# CATS-GS-MCU.net
KiCad netlist of a schematic drawn in Altium Designer
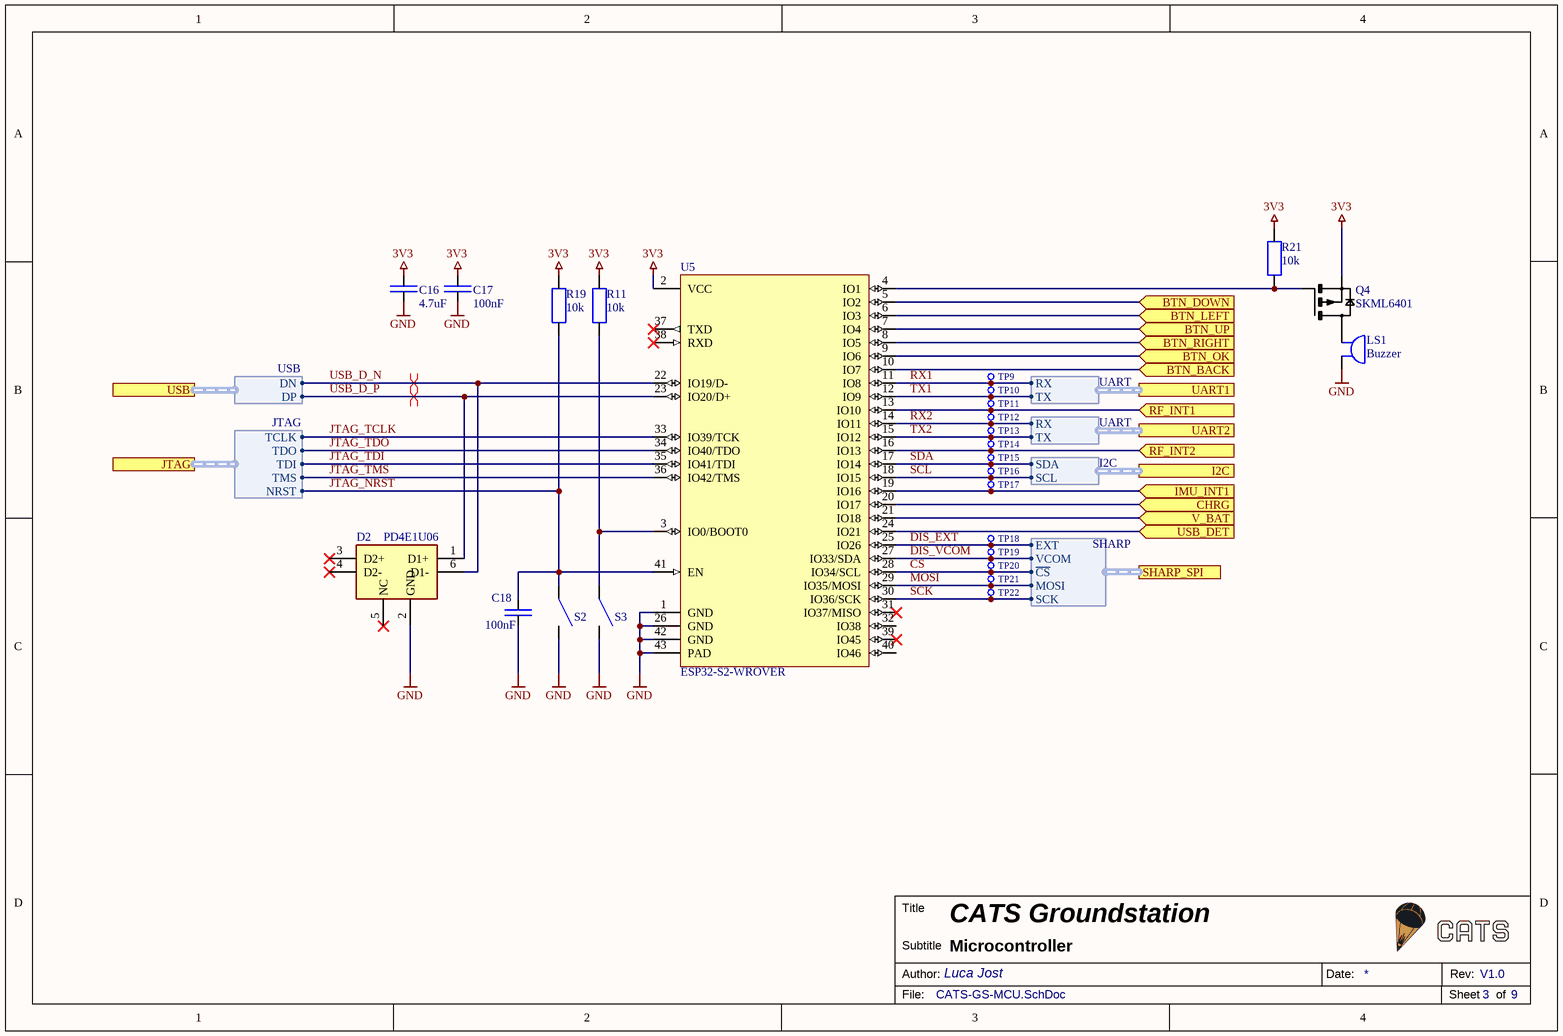
[diagram p0: CATS-GS-MCU.SchDoc]

(export (version "E")
  (design (tool "Eeschema 10.0.6"))
  (components
    (comp (ref "C16")
      (value "4.7uF")
      (footprint "SMD Keramikkondensator 0402")
      (description "SMD Ceramic Capacitor E6")
      (libsource (lib "CATS-EUROC") (part "E6 - 4.7uF"))
    )
    (comp (ref "C17")
      (value "100nF")
      (footprint "SMD Keramikkondensator 0402")
      (description "SMD Ceramic Capacitor E6")
      (libsource (lib "CATS-EUROC") (part "E6 - 100nF"))
    )
    (comp (ref "C18")
      (value "100nF")
      (footprint "SMD Keramikkondensator 0402")
      (description "SMD Ceramic Capacitor E6")
      (libsource (lib "CATS-EUROC") (part "E6 - 100nF"))
    )
    (comp (ref "D2")
      (value "PD4E1U06")
      (footprint "SMD IC SOT-363 (SC-70-6)")
      (description "Unidirectional 3A (8/20us) 15V (Typ) 6.5V 5.5V (Max) SOT-363 ESD Protection Devices ROHS")
      (libsource (lib "Fleet-Monitor") (part "PD4E1U06DCKR"))
    )
    (comp (ref "LS1")
      (value "Buzzer")
      (footprint "SMD BUZZER CMT-8504")
      (description "Buzzers Indicator, Internally Driven Piezo 12V 10mA 3kHz 100dB @ 12V, 10cm Through Hole PC Pins")
      (libsource (lib "Other") (part "Buzzer"))
    )
    (comp (ref "Q4")
      (value "SKML6401")
      (footprint "SMD MOSFET SOT-23")
      (description "P Channel MOSFET, 16V 3A, SOT-23")
      (libsource (lib "Electronic Switches") (part "SKML6401"))
    )
    (comp (ref "R11")
      (value "10k")
      (footprint "SMD Widerstand 0402")
      (description "SMD Chip Resistor E24")
      (libsource (lib "Resistors-E24") (part "E24 - 10k"))
    )
    (comp (ref "R19")
      (value "10k")
      (footprint "SMD Widerstand 0402")
      (description "SMD Chip Resistor E24")
      (libsource (lib "Resistors-E24") (part "E24 - 10k"))
    )
    (comp (ref "R21")
      (value "10k")
      (footprint "SMD Widerstand 0402")
      (description "SMD Chip Resistor E24")
      (libsource (lib "Resistors-E24") (part "E24 - 10k"))
    )
    (comp (ref "S2")
      (value "SMD-Button")
      (footprint "SMD Button 2.5x3x1.2")
      (description "Button SPST")
      (libsource (lib "CATS-EUROC") (part "Button 3mmx2.5mm"))
    )
    (comp (ref "S3")
      (value "SMD-Button")
      (footprint "SMD Button 2.5x3x1.2")
      (description "Button SPST")
      (libsource (lib "CATS-EUROC") (part "Button 3mmx2.5mm"))
    )
    (comp (ref "TP9")
      (value "X-TP")
      (footprint "SMD Testpoint 1mm")
      (description "Testpunkt")
      (libsource (lib "VLD-Monitor_V1.0") (part "X-TP"))
    )
    (comp (ref "TP10")
      (value "X-TP")
      (footprint "SMD Testpoint 1mm")
      (description "Testpunkt")
      (libsource (lib "VLD-Monitor_V1.0") (part "X-TP"))
    )
    (comp (ref "TP11")
      (value "X-TP")
      (footprint "SMD Testpoint 1mm")
      (description "Testpunkt")
      (libsource (lib "VLD-Monitor_V1.0") (part "X-TP"))
    )
    (comp (ref "TP12")
      (value "X-TP")
      (footprint "SMD Testpoint 1mm")
      (description "Testpunkt")
      (libsource (lib "VLD-Monitor_V1.0") (part "X-TP"))
    )
    (comp (ref "TP13")
      (value "X-TP")
      (footprint "SMD Testpoint 1mm")
      (description "Testpunkt")
      (libsource (lib "VLD-Monitor_V1.0") (part "X-TP"))
    )
    (comp (ref "TP14")
      (value "X-TP")
      (footprint "SMD Testpoint 1mm")
      (description "Testpunkt")
      (libsource (lib "VLD-Monitor_V1.0") (part "X-TP"))
    )
    (comp (ref "TP15")
      (value "X-TP")
      (footprint "SMD Testpoint 1mm")
      (description "Testpunkt")
      (libsource (lib "VLD-Monitor_V1.0") (part "X-TP"))
    )
    (comp (ref "TP16")
      (value "X-TP")
      (footprint "SMD Testpoint 1mm")
      (description "Testpunkt")
      (libsource (lib "VLD-Monitor_V1.0") (part "X-TP"))
    )
    (comp (ref "TP17")
      (value "X-TP")
      (footprint "SMD Testpoint 1mm")
      (description "Testpunkt")
      (libsource (lib "VLD-Monitor_V1.0") (part "X-TP"))
    )
    (comp (ref "TP18")
      (value "X-TP")
      (footprint "SMD Testpoint 1mm")
      (description "Testpunkt")
      (libsource (lib "VLD-Monitor_V1.0") (part "X-TP"))
    )
    (comp (ref "TP19")
      (value "X-TP")
      (footprint "SMD Testpoint 1mm")
      (description "Testpunkt")
      (libsource (lib "VLD-Monitor_V1.0") (part "X-TP"))
    )
    (comp (ref "TP20")
      (value "X-TP")
      (footprint "SMD Testpoint 1mm")
      (description "Testpunkt")
      (libsource (lib "VLD-Monitor_V1.0") (part "X-TP"))
    )
    (comp (ref "TP21")
      (value "X-TP")
      (footprint "SMD Testpoint 1mm")
      (description "Testpunkt")
      (libsource (lib "VLD-Monitor_V1.0") (part "X-TP"))
    )
    (comp (ref "TP22")
      (value "X-TP")
      (footprint "SMD Testpoint 1mm")
      (description "Testpunkt")
      (libsource (lib "VLD-Monitor_V1.0") (part "X-TP"))
    )
    (comp (ref "U5")
      (value "ESP32-S2-WROVER")
      (footprint "SMD ESP32-S2-WROOM")
      (description "WiFi 802.11b/g/n Transceiver Module 2.4GHz Antenna, Surface Mount")
      (libsource (lib "Microcontrollers") (part "ESP32-S2-WROVER"))
    )
  )
  (nets
    (net (code "6") (name "/BTN_BACK") (class "Default")
      (node (ref "U5") (pin "10") (pinfunction "IO7_10") (pintype "bidirectional"))
    )
    (net (code "7") (name "/BTN_DOWN") (class "Default")
      (node (ref "U5") (pin "5") (pinfunction "IO2_5") (pintype "bidirectional"))
    )
    (net (code "8") (name "/BTN_LEFT") (class "Default")
      (node (ref "U5") (pin "6") (pinfunction "IO3_6") (pintype "bidirectional"))
    )
    (net (code "9") (name "/BTN_OK") (class "Default")
      (node (ref "U5") (pin "9") (pinfunction "IO6_9") (pintype "bidirectional"))
    )
    (net (code "10") (name "/BTN_RIGHT") (class "Default")
      (node (ref "U5") (pin "8") (pinfunction "IO5_8") (pintype "bidirectional"))
    )
    (net (code "11") (name "/BTN_UP") (class "Default")
      (node (ref "U5") (pin "7") (pinfunction "IO4_7") (pintype "bidirectional"))
    )
    (net (code "12") (name "/CHRG") (class "Default")
      (node (ref "U5") (pin "20") (pinfunction "IO17_20") (pintype "bidirectional"))
    )
    (net (code "13") (name "/DIS_EXT") (class "Default")
      (node (ref "TP18") (pin "1") (pinfunction "1_1") (pintype "passive"))
      (node (ref "U5") (pin "25") (pinfunction "IO26_25") (pintype "bidirectional"))
    )
    (net (code "14") (name "/DIS_VCOM") (class "Default")
      (node (ref "TP19") (pin "1") (pinfunction "1_1") (pintype "passive"))
      (node (ref "U5") (pin "27") (pinfunction "IO33/SDA_27") (pintype "bidirectional"))
    )
    (net (code "15") (name "/IMU_INT1") (class "Default")
      (node (ref "TP17") (pin "1") (pinfunction "1_1") (pintype "passive"))
      (node (ref "U5") (pin "19") (pinfunction "IO16_19") (pintype "bidirectional"))
    )
    (net (code "16") (name "/JTAG_NRST") (class "Default")
      (node (ref "C18") (pin "2") (pinfunction "2_2") (pintype "passive"))
      (node (ref "R19") (pin "1") (pinfunction "1_1") (pintype "passive"))
      (node (ref "S2") (pin "1") (pinfunction "1_1") (pintype "passive"))
      (node (ref "U5") (pin "41") (pinfunction "EN_41") (pintype "input"))
    )
    (net (code "17") (name "/JTAG_TCLK") (class "Default")
      (node (ref "U5") (pin "33") (pinfunction "IO39/TCK_33") (pintype "bidirectional"))
    )
    (net (code "18") (name "/JTAG_TDI") (class "Default")
      (node (ref "U5") (pin "35") (pinfunction "IO41/TDI_35") (pintype "bidirectional"))
    )
    (net (code "19") (name "/JTAG_TDO") (class "Default")
      (node (ref "U5") (pin "34") (pinfunction "IO40/TDO_34") (pintype "bidirectional"))
    )
    (net (code "20") (name "/JTAG_TMS") (class "Default")
      (node (ref "U5") (pin "36") (pinfunction "IO42/TMS_36") (pintype "bidirectional"))
    )
    (net (code "21") (name "/MOSI") (class "Default")
      (node (ref "TP21") (pin "1") (pinfunction "1_1") (pintype "passive"))
      (node (ref "U5") (pin "29") (pinfunction "IO35/MOSI_29") (pintype "bidirectional"))
    )
    (net (code "22") (name "/RF_INT1") (class "Default")
      (node (ref "TP11") (pin "1") (pinfunction "1_1") (pintype "passive"))
      (node (ref "U5") (pin "13") (pinfunction "IO10_13") (pintype "bidirectional"))
    )
    (net (code "23") (name "/RF_INT2") (class "Default")
      (node (ref "TP14") (pin "1") (pinfunction "1_1") (pintype "passive"))
      (node (ref "U5") (pin "16") (pinfunction "IO13_16") (pintype "bidirectional"))
    )
    (net (code "24") (name "/RX1") (class "Default")
      (node (ref "TP9") (pin "1") (pinfunction "1_1") (pintype "passive"))
      (node (ref "U5") (pin "11") (pinfunction "IO8_11") (pintype "bidirectional"))
    )
    (net (code "25") (name "/RX2") (class "Default")
      (node (ref "TP12") (pin "1") (pinfunction "1_1") (pintype "passive"))
      (node (ref "U5") (pin "14") (pinfunction "IO11_14") (pintype "bidirectional"))
    )
    (net (code "26") (name "/SCK") (class "Default")
      (node (ref "TP22") (pin "1") (pinfunction "1_1") (pintype "passive"))
      (node (ref "U5") (pin "30") (pinfunction "IO36/SCK_30") (pintype "bidirectional"))
    )
    (net (code "27") (name "/SCL") (class "Default")
      (node (ref "TP16") (pin "1") (pinfunction "1_1") (pintype "passive"))
      (node (ref "U5") (pin "18") (pinfunction "IO15_18") (pintype "bidirectional"))
    )
    (net (code "28") (name "/SDA") (class "Default")
      (node (ref "TP15") (pin "1") (pinfunction "1_1") (pintype "passive"))
      (node (ref "U5") (pin "17") (pinfunction "IO14_17") (pintype "bidirectional"))
    )
    (net (code "29") (name "/TX1") (class "Default")
      (node (ref "TP10") (pin "1") (pinfunction "1_1") (pintype "passive"))
      (node (ref "U5") (pin "12") (pinfunction "IO9_12") (pintype "bidirectional"))
    )
    (net (code "30") (name "/TX2") (class "Default")
      (node (ref "TP13") (pin "1") (pinfunction "1_1") (pintype "passive"))
      (node (ref "U5") (pin "15") (pinfunction "IO12_15") (pintype "bidirectional"))
    )
    (net (code "31") (name "/USB_DET") (class "Default")
      (node (ref "U5") (pin "24") (pinfunction "IO21_24") (pintype "bidirectional"))
    )
    (net (code "32") (name "/USB_D_N") (class "Default")
      (node (ref "D2") (pin "6") (pinfunction "D1-_6") (pintype "passive"))
      (node (ref "U5") (pin "22") (pinfunction "IO19/D-_22") (pintype "bidirectional"))
    )
    (net (code "33") (name "/USB_D_P") (class "Default")
      (node (ref "D2") (pin "1") (pinfunction "D1+_1") (pintype "passive"))
      (node (ref "U5") (pin "23") (pinfunction "IO20/D+_23") (pintype "bidirectional"))
    )
    (net (code "34") (name "/V_BAT") (class "Default")
      (node (ref "U5") (pin "21") (pinfunction "IO18_21") (pintype "bidirectional"))
    )
    (net (code "40") (name "/~{CS}") (class "Default")
      (node (ref "TP20") (pin "1") (pinfunction "1_1") (pintype "passive"))
      (node (ref "U5") (pin "28") (pinfunction "IO34/SCL_28") (pintype "bidirectional"))
    )
    (net (code "41") (name "3V3") (class "Default")
      (node (ref "C16") (pin "2") (pinfunction "2_2") (pintype "passive"))
      (node (ref "C17") (pin "2") (pinfunction "2_2") (pintype "passive"))
      (node (ref "Q4") (pin "S") (pinfunction "S_S") (pintype "passive"))
      (node (ref "R11") (pin "2") (pinfunction "2_2") (pintype "passive"))
      (node (ref "R19") (pin "2") (pinfunction "2_2") (pintype "passive"))
      (node (ref "R21") (pin "2") (pinfunction "2_2") (pintype "passive"))
      (node (ref "U5") (pin "2") (pinfunction "VCC_2") (pintype "passive"))
    )
    (net (code "42") (name "GND") (class "Default")
      (node (ref "C16") (pin "1") (pinfunction "1_1") (pintype "passive"))
      (node (ref "C17") (pin "1") (pinfunction "1_1") (pintype "passive"))
      (node (ref "C18") (pin "1") (pinfunction "1_1") (pintype "passive"))
      (node (ref "D2") (pin "2") (pinfunction "GND_2") (pintype "passive"))
      (node (ref "LS1") (pin "2") (pinfunction "2_2") (pintype "passive"))
      (node (ref "S2") (pin "2") (pinfunction "2_2") (pintype "passive"))
      (node (ref "S3") (pin "2") (pinfunction "2_2") (pintype "passive"))
      (node (ref "U5") (pin "1") (pinfunction "GND_1") (pintype "passive"))
      (node (ref "U5") (pin "26") (pinfunction "GND_26") (pintype "passive"))
      (node (ref "U5") (pin "42") (pinfunction "GND_42") (pintype "passive"))
      (node (ref "U5") (pin "43") (pinfunction "PAD_43") (pintype "passive"))
    )
    (net (code "43") (name "Net-(LS1-Pad1)") (class "Default")
      (node (ref "LS1") (pin "1") (pinfunction "1_1") (pintype "passive"))
      (node (ref "Q4") (pin "D") (pinfunction "D_D") (pintype "passive"))
    )
    (net (code "44") (name "Net-(U5-IO0{slash}BOOT0)") (class "Default")
      (node (ref "R11") (pin "1") (pinfunction "1_1") (pintype "passive"))
      (node (ref "S3") (pin "1") (pinfunction "1_1") (pintype "passive"))
      (node (ref "U5") (pin "3") (pinfunction "IO0/BOOT0_3") (pintype "bidirectional"))
    )
    (net (code "45") (name "Net-(U5-IO1)") (class "Default")
      (node (ref "Q4") (pin "G") (pinfunction "G_G") (pintype "passive"))
      (node (ref "R21") (pin "1") (pinfunction "1_1") (pintype "passive"))
      (node (ref "U5") (pin "4") (pinfunction "IO1_4") (pintype "bidirectional"))
    )
    (net (code "46") (name "unconnected-(D2-D2+-Pad3)") (class "Default")
      (node (ref "D2") (pin "3") (pinfunction "D2+_3") (pintype "passive+no_connect"))
    )
    (net (code "47") (name "unconnected-(D2-D2--Pad4)") (class "Default")
      (node (ref "D2") (pin "4") (pinfunction "D2-_4") (pintype "passive+no_connect"))
    )
    (net (code "48") (name "unconnected-(D2-NC-Pad5)") (class "Default")
      (node (ref "D2") (pin "5") (pinfunction "NC_5") (pintype "passive+no_connect"))
    )
    (net (code "49") (name "unconnected-(U5-IO37{slash}MISO-Pad31)") (class "Default")
      (node (ref "U5") (pin "31") (pinfunction "IO37/MISO_31") (pintype "bidirectional+no_connect"))
    )
    (net (code "50") (name "unconnected-(U5-IO38-Pad32)") (class "Default")
      (node (ref "U5") (pin "32") (pinfunction "IO38_32") (pintype "bidirectional"))
    )
    (net (code "51") (name "unconnected-(U5-IO45-Pad39)") (class "Default")
      (node (ref "U5") (pin "39") (pinfunction "IO45_39") (pintype "bidirectional+no_connect"))
    )
    (net (code "52") (name "unconnected-(U5-IO46-Pad40)") (class "Default")
      (node (ref "U5") (pin "40") (pinfunction "IO46_40") (pintype "bidirectional"))
    )
    (net (code "53") (name "unconnected-(U5-RXD-Pad38)") (class "Default")
      (node (ref "U5") (pin "38") (pinfunction "RXD_38") (pintype "input+no_connect"))
    )
    (net (code "54") (name "unconnected-(U5-TXD-Pad37)") (class "Default")
      (node (ref "U5") (pin "37") (pinfunction "TXD_37") (pintype "output+no_connect"))
    )
  )
)
